# V1_3.net
KiCad netlist of a schematic drawn in EAGLE
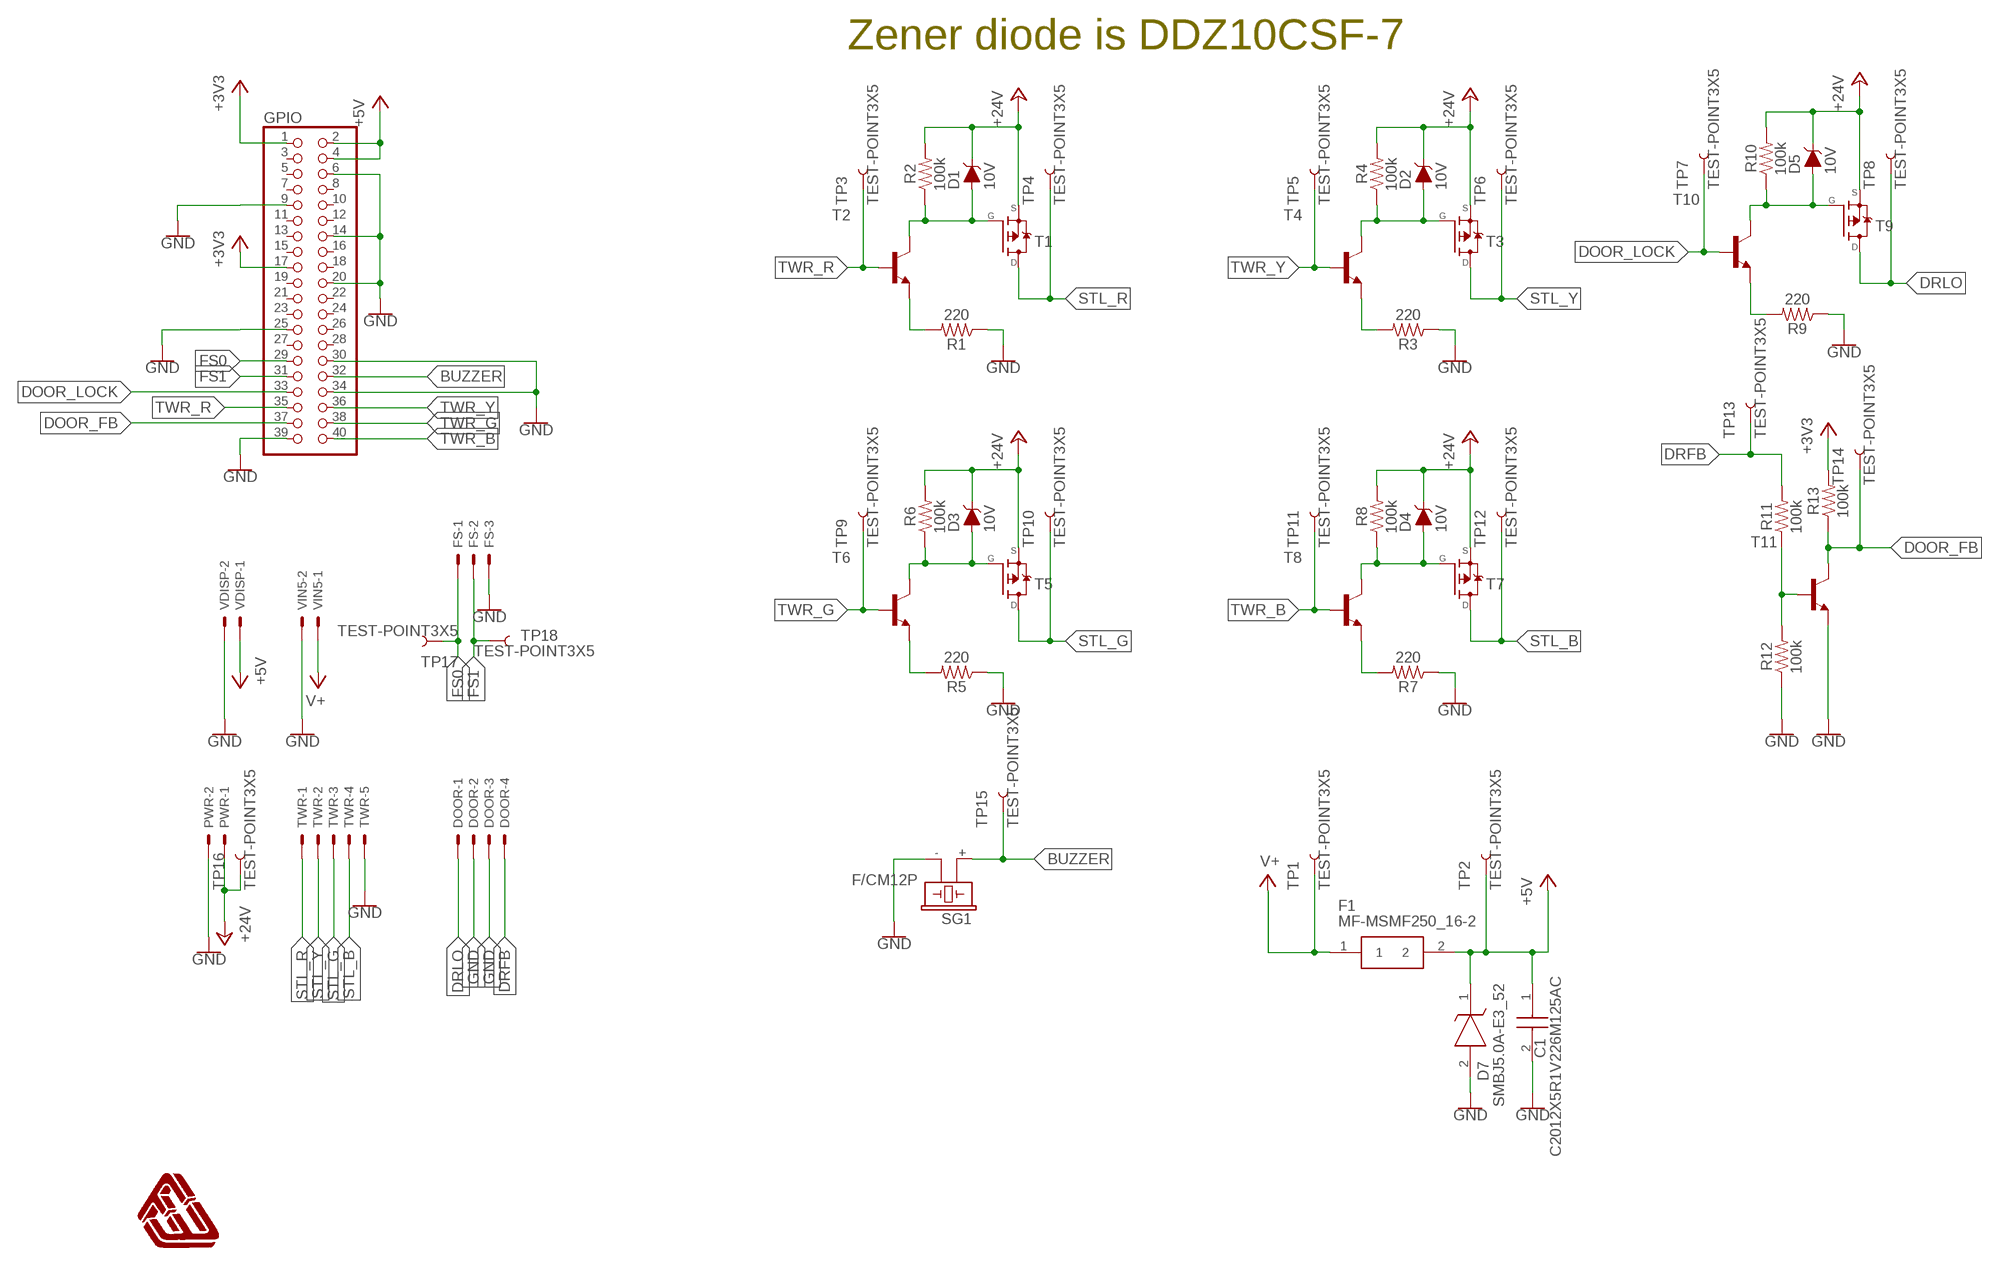
[diagram p0: schematic, sheet 1]

(export (version "E")
  (design (tool "Eeschema 10.0.6"))
  (components
    (comp (ref "C1")
      (value "C2012X5R1V226M125AC")
      (footprint "eagle-import:CAPC2012X145N")
      (fields
        (field (name "MOUSER_PART_NUMBER") "810-C2012X5R1V226MAC")
        (field (name "RS_PART_NUMBER") "9159334P")
      )
      (libsource (lib "eagle-import") (part "C2012X5R1V226M125AC"))
    )
    (comp (ref "D1")
      (value "10V")
      (footprint "eagle-import:PANASONIC_SMINI2-F5-B")
      (libsource (lib "eagle-import") (part "DIODE-ZENER-DZ2J150M0L"))
    )
    (comp (ref "D2")
      (value "10V")
      (footprint "eagle-import:PANASONIC_SMINI2-F5-B")
      (libsource (lib "eagle-import") (part "DIODE-ZENER-DZ2J150M0L"))
    )
    (comp (ref "D3")
      (value "10V")
      (footprint "eagle-import:PANASONIC_SMINI2-F5-B")
      (libsource (lib "eagle-import") (part "DIODE-ZENER-DZ2J150M0L"))
    )
    (comp (ref "D4")
      (value "10V")
      (footprint "eagle-import:PANASONIC_SMINI2-F5-B")
      (libsource (lib "eagle-import") (part "DIODE-ZENER-DZ2J150M0L"))
    )
    (comp (ref "D5")
      (value "10V")
      (footprint "eagle-import:PANASONIC_SMINI2-F5-B")
      (libsource (lib "eagle-import") (part "DIODE-ZENER-DZ2J150M0L"))
    )
    (comp (ref "D7")
      (value "SMBJ5.0A-E3_52")
      (footprint "eagle-import:DIOM5436X244N")
      (fields
        (field (name "MANUFACTURER_PART_NUMBER") "SMBJ5.0A-E3/52")
        (field (name "MOUSER_PART_NUMBER") "625-SMBJ5.0A-E3")
        (field (name "RS_PART_NUMBER") "1652507")
      )
      (libsource (lib "eagle-import") (part "SMBJ5.0A-E3_52"))
    )
    (comp (ref "DOOR")
      (value "JST-XH-04-PIN-LONG-PAD")
      (footprint "eagle-import:JST-XH-04-PACKAGE-LONG-PAD")
      (libsource (lib "eagle-import") (part "JST-XH-04-PIN-LONG-PAD"))
    )
    (comp (ref "F1")
      (value "MF-MSMF250_16-2")
      (footprint "eagle-import:FUSC4632X160N")
      (fields
        (field (name "MANUFACTURER_PART_NUMBER") "MF-MSMF250/16-2")
        (field (name "MOUSER_PART_NUMBER") "652-MF-MSMF250/16-2")
        (field (name "RS_PART_NUMBER") "6478229P")
      )
      (libsource (lib "eagle-import") (part "MF-MSMF250_16-2"))
    )
    (comp (ref "FS")
      (value "JST-XH-03-PIN-LONG-PAD")
      (footprint "eagle-import:JST-XH-03-PACKAGE-LONG-PAD")
      (libsource (lib "eagle-import") (part "JST-XH-03-PIN-LONG-PAD"))
    )
    (comp (ref "GPIO")
      (value "RASPBERRYPI_3B_GPIO")
      (footprint "eagle-import:RASPBERRYPI_3B_GPIO")
      (libsource (lib "eagle-import") (part "RASPBERRYPI_3B_GPIO"))
    )
    (comp (ref "PWR")
      (value "JST-XH-02-PIN-LONG-PAD")
      (footprint "eagle-import:JST-XH-02-PACKAGE-LONG-PAD")
      (libsource (lib "eagle-import") (part "JST-XH-02-PIN-LONG-PAD"))
    )
    (comp (ref "R1")
      (value "220")
      (footprint "eagle-import:0603")
      (libsource (lib "eagle-import") (part "100KOHM-0603-1/10W-1%"))
    )
    (comp (ref "R2")
      (value "100k")
      (footprint "eagle-import:0603")
      (libsource (lib "eagle-import") (part "100KOHM-0603-1/10W-1%"))
    )
    (comp (ref "R3")
      (value "220")
      (footprint "eagle-import:0603")
      (libsource (lib "eagle-import") (part "100KOHM-0603-1/10W-1%"))
    )
    (comp (ref "R4")
      (value "100k")
      (footprint "eagle-import:0603")
      (libsource (lib "eagle-import") (part "100KOHM-0603-1/10W-1%"))
    )
    (comp (ref "R5")
      (value "220")
      (footprint "eagle-import:0603")
      (libsource (lib "eagle-import") (part "100KOHM-0603-1/10W-1%"))
    )
    (comp (ref "R6")
      (value "100k")
      (footprint "eagle-import:0603")
      (libsource (lib "eagle-import") (part "100KOHM-0603-1/10W-1%"))
    )
    (comp (ref "R7")
      (value "220")
      (footprint "eagle-import:0603")
      (libsource (lib "eagle-import") (part "100KOHM-0603-1/10W-1%"))
    )
    (comp (ref "R8")
      (value "100k")
      (footprint "eagle-import:0603")
      (libsource (lib "eagle-import") (part "100KOHM-0603-1/10W-1%"))
    )
    (comp (ref "R9")
      (value "220")
      (footprint "eagle-import:0603")
      (libsource (lib "eagle-import") (part "100KOHM-0603-1/10W-1%"))
    )
    (comp (ref "R10")
      (value "100k")
      (footprint "eagle-import:0603")
      (libsource (lib "eagle-import") (part "100KOHM-0603-1/10W-1%"))
    )
    (comp (ref "R11")
      (value "100k")
      (footprint "eagle-import:0603")
      (libsource (lib "eagle-import") (part "100KOHM-0603-1/10W-1%"))
    )
    (comp (ref "R12")
      (value "100k")
      (footprint "eagle-import:0603")
      (libsource (lib "eagle-import") (part "100KOHM-0603-1/10W-1%"))
    )
    (comp (ref "R13")
      (value "100k")
      (footprint "eagle-import:0603")
      (libsource (lib "eagle-import") (part "100KOHM-0603-1/10W-1%"))
    )
    (comp (ref "SG1")
      (value "F/CM12P")
      (footprint "eagle-import:F_CM12P")
      (libsource (lib "eagle-import") (part "F/CM12P"))
    )
    (comp (ref "T1")
      (value "MOSFET_P_SOT223")
      (footprint "eagle-import:MOSFET_SOT223")
      (libsource (lib "eagle-import") (part "MOSFET_P_SOT223"))
    )
    (comp (ref "T2")
      (value "MMBT3904LT1-NPN-SOT23-BEC")
      (footprint "eagle-import:SOT23-BEC")
      (libsource (lib "eagle-import") (part "-NPN-SOT23-BECMMBT3904LT1"))
    )
    (comp (ref "T3")
      (value "MOSFET_P_SOT223")
      (footprint "eagle-import:MOSFET_SOT223")
      (libsource (lib "eagle-import") (part "MOSFET_P_SOT223"))
    )
    (comp (ref "T4")
      (value "MMBT3904LT1-NPN-SOT23-BEC")
      (footprint "eagle-import:SOT23-BEC")
      (libsource (lib "eagle-import") (part "-NPN-SOT23-BECMMBT3904LT1"))
    )
    (comp (ref "T5")
      (value "MOSFET_P_SOT223")
      (footprint "eagle-import:MOSFET_SOT223")
      (libsource (lib "eagle-import") (part "MOSFET_P_SOT223"))
    )
    (comp (ref "T6")
      (value "MMBT3904LT1-NPN-SOT23-BEC")
      (footprint "eagle-import:SOT23-BEC")
      (libsource (lib "eagle-import") (part "-NPN-SOT23-BECMMBT3904LT1"))
    )
    (comp (ref "T7")
      (value "MOSFET_P_SOT223")
      (footprint "eagle-import:MOSFET_SOT223")
      (libsource (lib "eagle-import") (part "MOSFET_P_SOT223"))
    )
    (comp (ref "T8")
      (value "MMBT3904LT1-NPN-SOT23-BEC")
      (footprint "eagle-import:SOT23-BEC")
      (libsource (lib "eagle-import") (part "-NPN-SOT23-BECMMBT3904LT1"))
    )
    (comp (ref "T9")
      (value "MOSFET_P_SOT223")
      (footprint "eagle-import:MOSFET_SOT223")
      (libsource (lib "eagle-import") (part "MOSFET_P_SOT223"))
    )
    (comp (ref "T10")
      (value "MMBT3904LT1-NPN-SOT23-BEC")
      (footprint "eagle-import:SOT23-BEC")
      (libsource (lib "eagle-import") (part "-NPN-SOT23-BECMMBT3904LT1"))
    )
    (comp (ref "T11")
      (value "MMBT3904LT1-NPN-SOT23-BEC")
      (footprint "eagle-import:SOT23-BEC")
      (libsource (lib "eagle-import") (part "-NPN-SOT23-BECMMBT3904LT1"))
    )
    (comp (ref "TP1")
      (value "TEST-POINT3X5")
      (footprint "eagle-import:PAD.03X.05")
      (libsource (lib "eagle-import") (part "TEST-POINT3X5"))
    )
    (comp (ref "TP2")
      (value "TEST-POINT3X5")
      (footprint "eagle-import:PAD.03X.05")
      (libsource (lib "eagle-import") (part "TEST-POINT3X5"))
    )
    (comp (ref "TP3")
      (value "TEST-POINT3X5")
      (footprint "eagle-import:PAD.03X.05")
      (libsource (lib "eagle-import") (part "TEST-POINT3X5"))
    )
    (comp (ref "TP4")
      (value "TEST-POINT3X5")
      (footprint "eagle-import:PAD.03X.05")
      (libsource (lib "eagle-import") (part "TEST-POINT3X5"))
    )
    (comp (ref "TP5")
      (value "TEST-POINT3X5")
      (footprint "eagle-import:PAD.03X.05")
      (libsource (lib "eagle-import") (part "TEST-POINT3X5"))
    )
    (comp (ref "TP6")
      (value "TEST-POINT3X5")
      (footprint "eagle-import:PAD.03X.05")
      (libsource (lib "eagle-import") (part "TEST-POINT3X5"))
    )
    (comp (ref "TP7")
      (value "TEST-POINT3X5")
      (footprint "eagle-import:PAD.03X.05")
      (libsource (lib "eagle-import") (part "TEST-POINT3X5"))
    )
    (comp (ref "TP8")
      (value "TEST-POINT3X5")
      (footprint "eagle-import:PAD.03X.05")
      (libsource (lib "eagle-import") (part "TEST-POINT3X5"))
    )
    (comp (ref "TP9")
      (value "TEST-POINT3X5")
      (footprint "eagle-import:PAD.03X.05")
      (libsource (lib "eagle-import") (part "TEST-POINT3X5"))
    )
    (comp (ref "TP10")
      (value "TEST-POINT3X5")
      (footprint "eagle-import:PAD.03X.05")
      (libsource (lib "eagle-import") (part "TEST-POINT3X5"))
    )
    (comp (ref "TP11")
      (value "TEST-POINT3X5")
      (footprint "eagle-import:PAD.03X.05")
      (libsource (lib "eagle-import") (part "TEST-POINT3X5"))
    )
    (comp (ref "TP12")
      (value "TEST-POINT3X5")
      (footprint "eagle-import:PAD.03X.05")
      (libsource (lib "eagle-import") (part "TEST-POINT3X5"))
    )
    (comp (ref "TP13")
      (value "TEST-POINT3X5")
      (footprint "eagle-import:PAD.03X.05")
      (libsource (lib "eagle-import") (part "TEST-POINT3X5"))
    )
    (comp (ref "TP14")
      (value "TEST-POINT3X5")
      (footprint "eagle-import:PAD.03X.05")
      (libsource (lib "eagle-import") (part "TEST-POINT3X5"))
    )
    (comp (ref "TP15")
      (value "TEST-POINT3X5")
      (footprint "eagle-import:PAD.03X.05")
      (libsource (lib "eagle-import") (part "TEST-POINT3X5"))
    )
    (comp (ref "TP16")
      (value "TEST-POINT3X5")
      (footprint "eagle-import:PAD.03X.05")
      (libsource (lib "eagle-import") (part "TEST-POINT3X5"))
    )
    (comp (ref "TP17")
      (value "TEST-POINT3X5")
      (footprint "eagle-import:PAD.03X.05")
      (libsource (lib "eagle-import") (part "TEST-POINT3X5"))
    )
    (comp (ref "TP18")
      (value "TEST-POINT3X5")
      (footprint "eagle-import:PAD.03X.05")
      (libsource (lib "eagle-import") (part "TEST-POINT3X5"))
    )
    (comp (ref "TWR")
      (value "JST-XH-05-PIN-LONG-PAD")
      (footprint "eagle-import:JST-XH-05-PACKAGE-LONG-PAD")
      (libsource (lib "eagle-import") (part "JST-XH-05-PIN-LONG-PAD"))
    )
    (comp (ref "U$5")
      (value "FWLOGO")
      (footprint "eagle-import:FWLOGO")
      (libsource (lib "eagle-import") (part "FWLOGO"))
    )
    (comp (ref "VDISP")
      (value "JST-XH-02-PIN-LONG-PAD")
      (footprint "eagle-import:JST-XH-02-PACKAGE-LONG-PAD")
      (libsource (lib "eagle-import") (part "JST-XH-02-PIN-LONG-PAD"))
    )
    (comp (ref "VIN5")
      (value "JST-XH-02-PIN-LONG-PAD")
      (footprint "eagle-import:JST-XH-02-PACKAGE-LONG-PAD")
      (libsource (lib "eagle-import") (part "JST-XH-02-PIN-LONG-PAD"))
    )
  )
  (nets
    (net (code "1") (name "+3V3") (class "Default")
      (node (ref "GPIO") (pin "1") (pinfunction "1_1") (pintype "passive"))
      (node (ref "GPIO") (pin "17") (pinfunction "17_17") (pintype "passive"))
      (node (ref "R13") (pin "2") (pinfunction "2_2") (pintype "passive"))
    )
    (net (code "2") (name "+5V") (class "Default")
      (node (ref "C1") (pin "1") (pinfunction "1_1") (pintype "bidirectional"))
      (node (ref "D7") (pin "1") (pinfunction "K_1") (pintype "bidirectional"))
      (node (ref "F1") (pin "2") (pinfunction "2_2") (pintype "bidirectional"))
      (node (ref "GPIO") (pin "2") (pinfunction "2_2") (pintype "passive"))
      (node (ref "GPIO") (pin "4") (pinfunction "4_4") (pintype "passive"))
      (node (ref "TP2") (pin "P$1") (pinfunction "1_P$1") (pintype "bidirectional"))
      (node (ref "VDISP") (pin "1") (pinfunction "S_1") (pintype "passive"))
    )
    (net (code "3") (name "+24V") (class "Default")
      (node (ref "D1") (pin "C") (pinfunction "C_C") (pintype "passive"))
      (node (ref "D2") (pin "C") (pinfunction "C_C") (pintype "passive"))
      (node (ref "D3") (pin "C") (pinfunction "C_C") (pintype "passive"))
      (node (ref "D4") (pin "C") (pinfunction "C_C") (pintype "passive"))
      (node (ref "D5") (pin "C") (pinfunction "C_C") (pintype "passive"))
      (node (ref "PWR") (pin "1") (pinfunction "S_1") (pintype "passive"))
      (node (ref "R10") (pin "2") (pinfunction "2_2") (pintype "passive"))
      (node (ref "R2") (pin "2") (pinfunction "2_2") (pintype "passive"))
      (node (ref "R4") (pin "2") (pinfunction "2_2") (pintype "passive"))
      (node (ref "R6") (pin "2") (pinfunction "2_2") (pintype "passive"))
      (node (ref "R8") (pin "2") (pinfunction "2_2") (pintype "passive"))
      (node (ref "T1") (pin "3") (pinfunction "S_3") (pintype "passive"))
      (node (ref "T3") (pin "3") (pinfunction "S_3") (pintype "passive"))
      (node (ref "T5") (pin "3") (pinfunction "S_3") (pintype "passive"))
      (node (ref "T7") (pin "3") (pinfunction "S_3") (pintype "passive"))
      (node (ref "T9") (pin "3") (pinfunction "S_3") (pintype "passive"))
      (node (ref "TP16") (pin "P$1") (pinfunction "1_P$1") (pintype "bidirectional"))
    )
    (net (code "4") (name "BUZZER") (class "Default")
      (node (ref "GPIO") (pin "32") (pinfunction "32_32") (pintype "passive"))
      (node (ref "SG1") (pin "+") (pinfunction "1_+") (pintype "passive"))
      (node (ref "TP15") (pin "P$1") (pinfunction "1_P$1") (pintype "bidirectional"))
    )
    (net (code "5") (name "DOOR_FB") (class "Default")
      (node (ref "GPIO") (pin "37") (pinfunction "37_37") (pintype "passive"))
      (node (ref "R13") (pin "1") (pinfunction "1_1") (pintype "passive"))
      (node (ref "T11") (pin "C") (pinfunction "C_C") (pintype "passive"))
      (node (ref "TP14") (pin "P$1") (pinfunction "1_P$1") (pintype "bidirectional"))
    )
    (net (code "6") (name "DOOR_LOCK") (class "Default")
      (node (ref "GPIO") (pin "33") (pinfunction "33_33") (pintype "passive"))
      (node (ref "T10") (pin "B") (pinfunction "B_B") (pintype "passive"))
      (node (ref "TP7") (pin "P$1") (pinfunction "1_P$1") (pintype "bidirectional"))
    )
    (net (code "7") (name "DRFB") (class "Default")
      (node (ref "DOOR") (pin "4") (pinfunction "S_4") (pintype "passive"))
      (node (ref "R11") (pin "2") (pinfunction "2_2") (pintype "passive"))
      (node (ref "TP13") (pin "P$1") (pinfunction "1_P$1") (pintype "bidirectional"))
    )
    (net (code "8") (name "DRLO") (class "Default")
      (node (ref "DOOR") (pin "1") (pinfunction "S_1") (pintype "passive"))
      (node (ref "T9") (pin "2") (pinfunction "D_2") (pintype "passive"))
      (node (ref "T9") (pin "4") (pinfunction "D_4") (pintype "passive"))
      (node (ref "TP8") (pin "P$1") (pinfunction "1_P$1") (pintype "bidirectional"))
    )
    (net (code "9") (name "FS0") (class "Default")
      (node (ref "FS") (pin "1") (pinfunction "S_1") (pintype "passive"))
      (node (ref "GPIO") (pin "29") (pinfunction "29_29") (pintype "passive"))
      (node (ref "TP17") (pin "P$1") (pinfunction "1_P$1") (pintype "bidirectional"))
    )
    (net (code "10") (name "FS1") (class "Default")
      (node (ref "FS") (pin "2") (pinfunction "S_2") (pintype "passive"))
      (node (ref "GPIO") (pin "31") (pinfunction "31_31") (pintype "passive"))
      (node (ref "TP18") (pin "P$1") (pinfunction "1_P$1") (pintype "bidirectional"))
    )
    (net (code "11") (name "GND") (class "Default")
      (node (ref "C1") (pin "2") (pinfunction "2_2") (pintype "bidirectional"))
      (node (ref "D7") (pin "2") (pinfunction "A_2") (pintype "bidirectional"))
      (node (ref "DOOR") (pin "2") (pinfunction "S_2") (pintype "passive"))
      (node (ref "DOOR") (pin "3") (pinfunction "S_3") (pintype "passive"))
      (node (ref "FS") (pin "3") (pinfunction "S_3") (pintype "passive"))
      (node (ref "GPIO") (pin "14") (pinfunction "14_14") (pintype "passive"))
      (node (ref "GPIO") (pin "20") (pinfunction "20_20") (pintype "passive"))
      (node (ref "GPIO") (pin "25") (pinfunction "25_25") (pintype "passive"))
      (node (ref "GPIO") (pin "30") (pinfunction "30_30") (pintype "passive"))
      (node (ref "GPIO") (pin "34") (pinfunction "34_34") (pintype "passive"))
      (node (ref "GPIO") (pin "39") (pinfunction "39_39") (pintype "passive"))
      (node (ref "GPIO") (pin "6") (pinfunction "6_6") (pintype "passive"))
      (node (ref "GPIO") (pin "9") (pinfunction "9_9") (pintype "passive"))
      (node (ref "PWR") (pin "2") (pinfunction "S_2") (pintype "passive"))
      (node (ref "R1") (pin "1") (pinfunction "1_1") (pintype "passive"))
      (node (ref "R12") (pin "1") (pinfunction "1_1") (pintype "passive"))
      (node (ref "R3") (pin "1") (pinfunction "1_1") (pintype "passive"))
      (node (ref "R5") (pin "1") (pinfunction "1_1") (pintype "passive"))
      (node (ref "R7") (pin "1") (pinfunction "1_1") (pintype "passive"))
      (node (ref "R9") (pin "1") (pinfunction "1_1") (pintype "passive"))
      (node (ref "SG1") (pin "-") (pinfunction "2_-") (pintype "passive"))
      (node (ref "T11") (pin "E") (pinfunction "E_E") (pintype "passive"))
      (node (ref "TWR") (pin "5") (pinfunction "S_5") (pintype "passive"))
      (node (ref "VDISP") (pin "2") (pinfunction "S_2") (pintype "passive"))
      (node (ref "VIN5") (pin "2") (pinfunction "S_2") (pintype "passive"))
    )
    (net (code "12") (name "Net-(R1-Pad2)") (class "Default")
      (node (ref "R1") (pin "2") (pinfunction "2_2") (pintype "passive"))
      (node (ref "T2") (pin "E") (pinfunction "E_E") (pintype "passive"))
    )
    (net (code "13") (name "Net-(R3-Pad2)") (class "Default")
      (node (ref "R3") (pin "2") (pinfunction "2_2") (pintype "passive"))
      (node (ref "T4") (pin "E") (pinfunction "E_E") (pintype "passive"))
    )
    (net (code "14") (name "Net-(R5-Pad2)") (class "Default")
      (node (ref "R5") (pin "2") (pinfunction "2_2") (pintype "passive"))
      (node (ref "T6") (pin "E") (pinfunction "E_E") (pintype "passive"))
    )
    (net (code "15") (name "Net-(R7-Pad2)") (class "Default")
      (node (ref "R7") (pin "2") (pinfunction "2_2") (pintype "passive"))
      (node (ref "T8") (pin "E") (pinfunction "E_E") (pintype "passive"))
    )
    (net (code "16") (name "Net-(R9-Pad2)") (class "Default")
      (node (ref "R9") (pin "2") (pinfunction "2_2") (pintype "passive"))
      (node (ref "T10") (pin "E") (pinfunction "E_E") (pintype "passive"))
    )
    (net (code "17") (name "Net-(R11-Pad1)") (class "Default")
      (node (ref "R11") (pin "1") (pinfunction "1_1") (pintype "passive"))
      (node (ref "R12") (pin "2") (pinfunction "2_2") (pintype "passive"))
      (node (ref "T11") (pin "B") (pinfunction "B_B") (pintype "passive"))
    )
    (net (code "18") (name "Net-(T1-G)") (class "Default")
      (node (ref "D1") (pin "A") (pinfunction "A_A") (pintype "passive"))
      (node (ref "R2") (pin "1") (pinfunction "1_1") (pintype "passive"))
      (node (ref "T1") (pin "1") (pinfunction "G_1") (pintype "passive"))
      (node (ref "T2") (pin "C") (pinfunction "C_C") (pintype "passive"))
    )
    (net (code "19") (name "Net-(T3-G)") (class "Default")
      (node (ref "D2") (pin "A") (pinfunction "A_A") (pintype "passive"))
      (node (ref "R4") (pin "1") (pinfunction "1_1") (pintype "passive"))
      (node (ref "T3") (pin "1") (pinfunction "G_1") (pintype "passive"))
      (node (ref "T4") (pin "C") (pinfunction "C_C") (pintype "passive"))
    )
    (net (code "20") (name "Net-(T5-G)") (class "Default")
      (node (ref "D3") (pin "A") (pinfunction "A_A") (pintype "passive"))
      (node (ref "R6") (pin "1") (pinfunction "1_1") (pintype "passive"))
      (node (ref "T5") (pin "1") (pinfunction "G_1") (pintype "passive"))
      (node (ref "T6") (pin "C") (pinfunction "C_C") (pintype "passive"))
    )
    (net (code "21") (name "Net-(T7-G)") (class "Default")
      (node (ref "D4") (pin "A") (pinfunction "A_A") (pintype "passive"))
      (node (ref "R8") (pin "1") (pinfunction "1_1") (pintype "passive"))
      (node (ref "T7") (pin "1") (pinfunction "G_1") (pintype "passive"))
      (node (ref "T8") (pin "C") (pinfunction "C_C") (pintype "passive"))
    )
    (net (code "22") (name "Net-(T9-G)") (class "Default")
      (node (ref "D5") (pin "A") (pinfunction "A_A") (pintype "passive"))
      (node (ref "R10") (pin "1") (pinfunction "1_1") (pintype "passive"))
      (node (ref "T10") (pin "C") (pinfunction "C_C") (pintype "passive"))
      (node (ref "T9") (pin "1") (pinfunction "G_1") (pintype "passive"))
    )
    (net (code "23") (name "STL_B") (class "Default")
      (node (ref "T7") (pin "2") (pinfunction "D_2") (pintype "passive"))
      (node (ref "T7") (pin "4") (pinfunction "D_4") (pintype "passive"))
      (node (ref "TP12") (pin "P$1") (pinfunction "1_P$1") (pintype "bidirectional"))
      (node (ref "TWR") (pin "4") (pinfunction "S_4") (pintype "passive"))
    )
    (net (code "24") (name "STL_G") (class "Default")
      (node (ref "T5") (pin "2") (pinfunction "D_2") (pintype "passive"))
      (node (ref "T5") (pin "4") (pinfunction "D_4") (pintype "passive"))
      (node (ref "TP10") (pin "P$1") (pinfunction "1_P$1") (pintype "bidirectional"))
      (node (ref "TWR") (pin "3") (pinfunction "S_3") (pintype "passive"))
    )
    (net (code "25") (name "STL_R") (class "Default")
      (node (ref "T1") (pin "2") (pinfunction "D_2") (pintype "passive"))
      (node (ref "T1") (pin "4") (pinfunction "D_4") (pintype "passive"))
      (node (ref "TP4") (pin "P$1") (pinfunction "1_P$1") (pintype "bidirectional"))
      (node (ref "TWR") (pin "1") (pinfunction "S_1") (pintype "passive"))
    )
    (net (code "26") (name "STL_Y") (class "Default")
      (node (ref "T3") (pin "2") (pinfunction "D_2") (pintype "passive"))
      (node (ref "T3") (pin "4") (pinfunction "D_4") (pintype "passive"))
      (node (ref "TP6") (pin "P$1") (pinfunction "1_P$1") (pintype "bidirectional"))
      (node (ref "TWR") (pin "2") (pinfunction "S_2") (pintype "passive"))
    )
    (net (code "27") (name "TWR_B") (class "Default")
      (node (ref "GPIO") (pin "40") (pinfunction "40_40") (pintype "passive"))
      (node (ref "T8") (pin "B") (pinfunction "B_B") (pintype "passive"))
      (node (ref "TP11") (pin "P$1") (pinfunction "1_P$1") (pintype "bidirectional"))
    )
    (net (code "28") (name "TWR_G") (class "Default")
      (node (ref "GPIO") (pin "38") (pinfunction "38_38") (pintype "passive"))
      (node (ref "T6") (pin "B") (pinfunction "B_B") (pintype "passive"))
      (node (ref "TP9") (pin "P$1") (pinfunction "1_P$1") (pintype "bidirectional"))
    )
    (net (code "29") (name "TWR_R") (class "Default")
      (node (ref "GPIO") (pin "35") (pinfunction "35_35") (pintype "passive"))
      (node (ref "T2") (pin "B") (pinfunction "B_B") (pintype "passive"))
      (node (ref "TP3") (pin "P$1") (pinfunction "1_P$1") (pintype "bidirectional"))
    )
    (net (code "30") (name "TWR_Y") (class "Default")
      (node (ref "GPIO") (pin "36") (pinfunction "36_36") (pintype "passive"))
      (node (ref "T4") (pin "B") (pinfunction "B_B") (pintype "passive"))
      (node (ref "TP5") (pin "P$1") (pinfunction "1_P$1") (pintype "bidirectional"))
    )
    (net (code "31") (name "V+") (class "Default")
      (node (ref "F1") (pin "1") (pinfunction "1_1") (pintype "bidirectional"))
      (node (ref "TP1") (pin "P$1") (pinfunction "1_P$1") (pintype "bidirectional"))
      (node (ref "VIN5") (pin "1") (pinfunction "S_1") (pintype "passive"))
    )
    (net (code "32") (name "unconnected-(GPIO-Pad3)") (class "Default")
      (node (ref "GPIO") (pin "3") (pinfunction "3_3") (pintype "passive"))
    )
    (net (code "33") (name "unconnected-(GPIO-Pad5)") (class "Default")
      (node (ref "GPIO") (pin "5") (pinfunction "5_5") (pintype "passive"))
    )
    (net (code "34") (name "unconnected-(GPIO-Pad7)") (class "Default")
      (node (ref "GPIO") (pin "7") (pinfunction "7_7") (pintype "passive"))
    )
    (net (code "35") (name "unconnected-(GPIO-Pad8)") (class "Default")
      (node (ref "GPIO") (pin "8") (pinfunction "8_8") (pintype "passive"))
    )
    (net (code "36") (name "unconnected-(GPIO-Pad10)") (class "Default")
      (node (ref "GPIO") (pin "10") (pinfunction "10_10") (pintype "passive"))
    )
    (net (code "37") (name "unconnected-(GPIO-Pad11)") (class "Default")
      (node (ref "GPIO") (pin "11") (pinfunction "11_11") (pintype "passive"))
    )
    (net (code "38") (name "unconnected-(GPIO-Pad12)") (class "Default")
      (node (ref "GPIO") (pin "12") (pinfunction "12_12") (pintype "passive"))
    )
    (net (code "39") (name "unconnected-(GPIO-Pad13)") (class "Default")
      (node (ref "GPIO") (pin "13") (pinfunction "13_13") (pintype "passive"))
    )
    (net (code "40") (name "unconnected-(GPIO-Pad15)") (class "Default")
      (node (ref "GPIO") (pin "15") (pinfunction "15_15") (pintype "passive"))
    )
    (net (code "41") (name "unconnected-(GPIO-Pad16)") (class "Default")
      (node (ref "GPIO") (pin "16") (pinfunction "16_16") (pintype "passive"))
    )
    (net (code "42") (name "unconnected-(GPIO-Pad18)") (class "Default")
      (node (ref "GPIO") (pin "18") (pinfunction "18_18") (pintype "passive"))
    )
    (net (code "43") (name "unconnected-(GPIO-Pad19)") (class "Default")
      (node (ref "GPIO") (pin "19") (pinfunction "19_19") (pintype "passive"))
    )
    (net (code "44") (name "unconnected-(GPIO-Pad21)") (class "Default")
      (node (ref "GPIO") (pin "21") (pinfunction "21_21") (pintype "passive"))
    )
    (net (code "45") (name "unconnected-(GPIO-Pad22)") (class "Default")
      (node (ref "GPIO") (pin "22") (pinfunction "22_22") (pintype "passive"))
    )
    (net (code "46") (name "unconnected-(GPIO-Pad23)") (class "Default")
      (node (ref "GPIO") (pin "23") (pinfunction "23_23") (pintype "passive"))
    )
    (net (code "47") (name "unconnected-(GPIO-Pad24)") (class "Default")
      (node (ref "GPIO") (pin "24") (pinfunction "24_24") (pintype "passive"))
    )
    (net (code "48") (name "unconnected-(GPIO-Pad26)") (class "Default")
      (node (ref "GPIO") (pin "26") (pinfunction "26_26") (pintype "passive"))
    )
    (net (code "49") (name "unconnected-(GPIO-Pad27)") (class "Default")
      (node (ref "GPIO") (pin "27") (pinfunction "27_27") (pintype "passive"))
    )
    (net (code "50") (name "unconnected-(GPIO-Pad28)") (class "Default")
      (node (ref "GPIO") (pin "28") (pinfunction "28_28") (pintype "passive"))
    )
  )
)
